# Power.net
KiCad netlist of a schematic drawn in Altium Designer
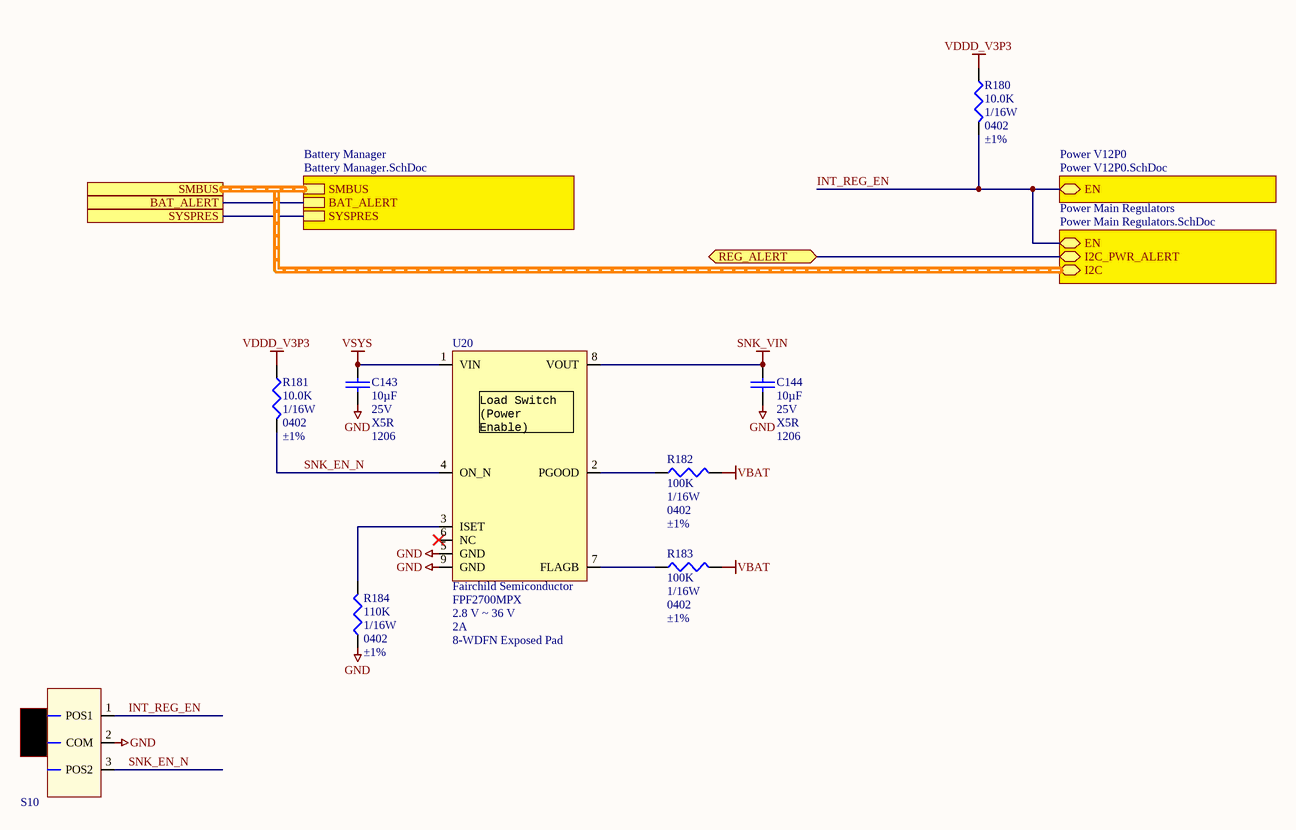
[diagram p0: Power.SchDoc]

(export (version "E")
  (design (tool "Eeschema 10.0.6"))
  (components
    (comp (ref "C143")
      (value "10µF")
      (footprint "CAP-1206")
      (description "CAP CER 10UF 25V X5R 1206")
      (fields
        (field (name "MANUFACTURER") "Murata Electronics North America")
        (field (name "MANUFACTURER PART NUMBER") "GRM31CR61E106MA12L")
        (field (name "CAPACITANCE") "10µF")
        (field (name "VOLTAGE - RATED") "25V")
        (field (name "TEMPERATURE COEFFICIENT") "X5R")
        (field (name "PACKAGE / CASE") "1206")
      )
      (libsource (lib "Main Library") (part "C_1206_10UF_25V"))
    )
    (comp (ref "C144")
      (value "10µF")
      (footprint "CAP-1206")
      (description "CAP CER 10UF 25V X5R 1206")
      (fields
        (field (name "MANUFACTURER") "Murata Electronics North America")
        (field (name "MANUFACTURER PART NUMBER") "GRM31CR61E106MA12L")
        (field (name "CAPACITANCE") "10µF")
        (field (name "VOLTAGE - RATED") "25V")
        (field (name "TEMPERATURE COEFFICIENT") "X5R")
        (field (name "PACKAGE / CASE") "1206")
      )
      (libsource (lib "Main Library") (part "C_1206_10UF_25V"))
    )
    (comp (ref "R180")
      (value "R_0402_10.0K")
      (footprint "R_0402")
      (description "RES 10.0K OHM 1/16W 1% 0402 SMD")
      (fields
        (field (name "MANUFACTURER") "Stackpole Electronics Inc")
        (field (name "MANUFACTURER PART NUMBER") "RMCF0402FT10K0")
        (field (name "RESISTANCE IN OHMS") "10.0K")
        (field (name "POWER (WATTS)") "1/16W")
        (field (name "CASE") "0402")
        (field (name "TOLERANCE") "±1%")
      )
      (libsource (lib "Cospan Design") (part "R_0402_10.0K"))
    )
    (comp (ref "R181")
      (value "R_0402_10.0K")
      (footprint "R_0402")
      (description "RES 10.0K OHM 1/16W 1% 0402 SMD")
      (fields
        (field (name "MANUFACTURER") "Stackpole Electronics Inc")
        (field (name "MANUFACTURER PART NUMBER") "RMCF0402FT10K0")
        (field (name "RESISTANCE IN OHMS") "10.0K")
        (field (name "POWER (WATTS)") "1/16W")
        (field (name "CASE") "0402")
        (field (name "TOLERANCE") "±1%")
      )
      (libsource (lib "Cospan Design") (part "R_0402_10.0K"))
    )
    (comp (ref "R182")
      (value "R_0402_100K")
      (footprint "R_0402")
      (description "RES SMD 100K OHM 1% 1/16W 0402")
      (fields
        (field (name "MANUFACTURER") "Yageo")
        (field (name "MANUFACTURER PART NUMBER") "RC0402FR-07100KL")
        (field (name "RESISTANCE IN OHMS") "100K")
        (field (name "POWER (WATTS)") "1/16W")
        (field (name "CASE") "0402")
        (field (name "TOLERANCE") "±1%")
      )
      (libsource (lib "Cospan Design") (part "R_0402_100K"))
    )
    (comp (ref "R183")
      (value "R_0402_100K")
      (footprint "R_0402")
      (description "RES SMD 100K OHM 1% 1/16W 0402")
      (fields
        (field (name "MANUFACTURER") "Yageo")
        (field (name "MANUFACTURER PART NUMBER") "RC0402FR-07100KL")
        (field (name "RESISTANCE IN OHMS") "100K")
        (field (name "POWER (WATTS)") "1/16W")
        (field (name "CASE") "0402")
        (field (name "TOLERANCE") "±1%")
      )
      (libsource (lib "Cospan Design") (part "R_0402_100K"))
    )
    (comp (ref "R184")
      (value "110K")
      (footprint "R_0402")
      (description "RES 110K OHM 1/10W 1% 0402 SMD")
      (fields
        (field (name "MANUFACTURER") "Panasonic Electronic Components")
        (field (name "MANUFACTURER PART NUMBER") "ERJ-2RKF1103X")
        (field (name "RESISTANCE IN OHMS") "110K")
        (field (name "POWER (WATTS)") "1/16W")
        (field (name "CASE") "0402")
        (field (name "TOLERANCE") "±1%")
      )
      (libsource (lib "Main Library") (part "R_0402_110K"))
    )
    (comp (ref "S10")
      (value "Micro Slide Switch")
      (footprint "PCM_SMD_SWITCH")
      (description "SWITCH SLIDE SPDT 300MA 6V")
      (fields
        (field (name "MANUFACTURER") "C&K Components")
        (field (name "MANUFACTURER PART NUMBER") "PCM12SMTR")
      )
      (libsource (lib "Cospan Design") (part "S_MICRO_SLIDE_SWITCH_ON_OFF"))
    )
    (comp (ref "U20")
      (value "U_FPF2700MPX")
      (footprint "SON65P300X80_HS-9N")
      (description "IC LOAD SWITCH CURR LIMIT 8-MLP")
      (fields
        (field (name "MANUFACTURER") "Fairchild Semiconductor")
        (field (name "MANUFACTURER PART NUMBER") "FPF2700MPX")
        (field (name "VOLTAGE - LOAD") "2.8 V ~ 36 V")
        (field (name "CURRENT - OUTPUT (MAX)") "2A")
        (field (name "PACKAGE / CASE") "8-WDFN Exposed Pad")
      )
      (libsource (lib "Cospan Design") (part "U_FPF2700MPX"))
    )
  )
  (nets
    (net (code "4") (name "/INT_REG_EN") (class "Default")
      (node (ref "R180") (pin "1") (pinfunction "1_1") (pintype "passive"))
      (node (ref "S10") (pin "1") (pinfunction "POS1_1") (pintype "passive"))
    )
    (net (code "7") (name "/SNK_EN_N") (class "Default")
      (node (ref "R181") (pin "1") (pinfunction "1_1") (pintype "passive"))
      (node (ref "S10") (pin "3") (pinfunction "POS2_3") (pintype "passive"))
      (node (ref "U20") (pin "4") (pinfunction "ON_N_4") (pintype "passive"))
    )
    (net (code "9") (name "GND") (class "Default")
      (node (ref "C143") (pin "1") (pinfunction "1_1") (pintype "passive"))
      (node (ref "C144") (pin "1") (pinfunction "1_1") (pintype "passive"))
      (node (ref "R184") (pin "2") (pinfunction "2_2") (pintype "passive"))
      (node (ref "S10") (pin "2") (pinfunction "COM_2") (pintype "passive"))
      (node (ref "U20") (pin "5") (pinfunction "GND_5") (pintype "passive"))
      (node (ref "U20") (pin "9") (pinfunction "GND_9") (pintype "passive"))
    )
    (net (code "10") (name "Net-(U20-FLAGB)") (class "Default")
      (node (ref "R183") (pin "2") (pinfunction "2_2") (pintype "passive"))
      (node (ref "U20") (pin "7") (pinfunction "FLAGB_7") (pintype "passive"))
    )
    (net (code "11") (name "Net-(U20-ISET)") (class "Default")
      (node (ref "R184") (pin "1") (pinfunction "1_1") (pintype "passive"))
      (node (ref "U20") (pin "3") (pinfunction "ISET_3") (pintype "passive"))
    )
    (net (code "12") (name "Net-(U20-PGOOD)") (class "Default")
      (node (ref "R182") (pin "2") (pinfunction "2_2") (pintype "passive"))
      (node (ref "U20") (pin "2") (pinfunction "PGOOD_2") (pintype "passive"))
    )
    (net (code "13") (name "SNK_VIN") (class "Default")
      (node (ref "C144") (pin "2") (pinfunction "2_2") (pintype "passive"))
      (node (ref "U20") (pin "8") (pinfunction "VOUT_8") (pintype "passive"))
    )
    (net (code "14") (name "VBAT") (class "Default")
      (node (ref "R182") (pin "1") (pinfunction "1_1") (pintype "passive"))
      (node (ref "R183") (pin "1") (pinfunction "1_1") (pintype "passive"))
    )
    (net (code "15") (name "VDDD_V3P3") (class "Default")
      (node (ref "R180") (pin "2") (pinfunction "2_2") (pintype "passive"))
      (node (ref "R181") (pin "2") (pinfunction "2_2") (pintype "passive"))
    )
    (net (code "16") (name "VSYS") (class "Default")
      (node (ref "C143") (pin "2") (pinfunction "2_2") (pintype "passive"))
      (node (ref "U20") (pin "1") (pinfunction "VIN_1") (pintype "passive"))
    )
    (net (code "17") (name "unconnected-(U20-NC-Pad6)") (class "Default")
      (node (ref "U20") (pin "6") (pinfunction "NC_6") (pintype "passive+no_connect"))
    )
  )
)
